# ctecka_stolni.net
KiCad netlist of a schematic drawn in EAGLE
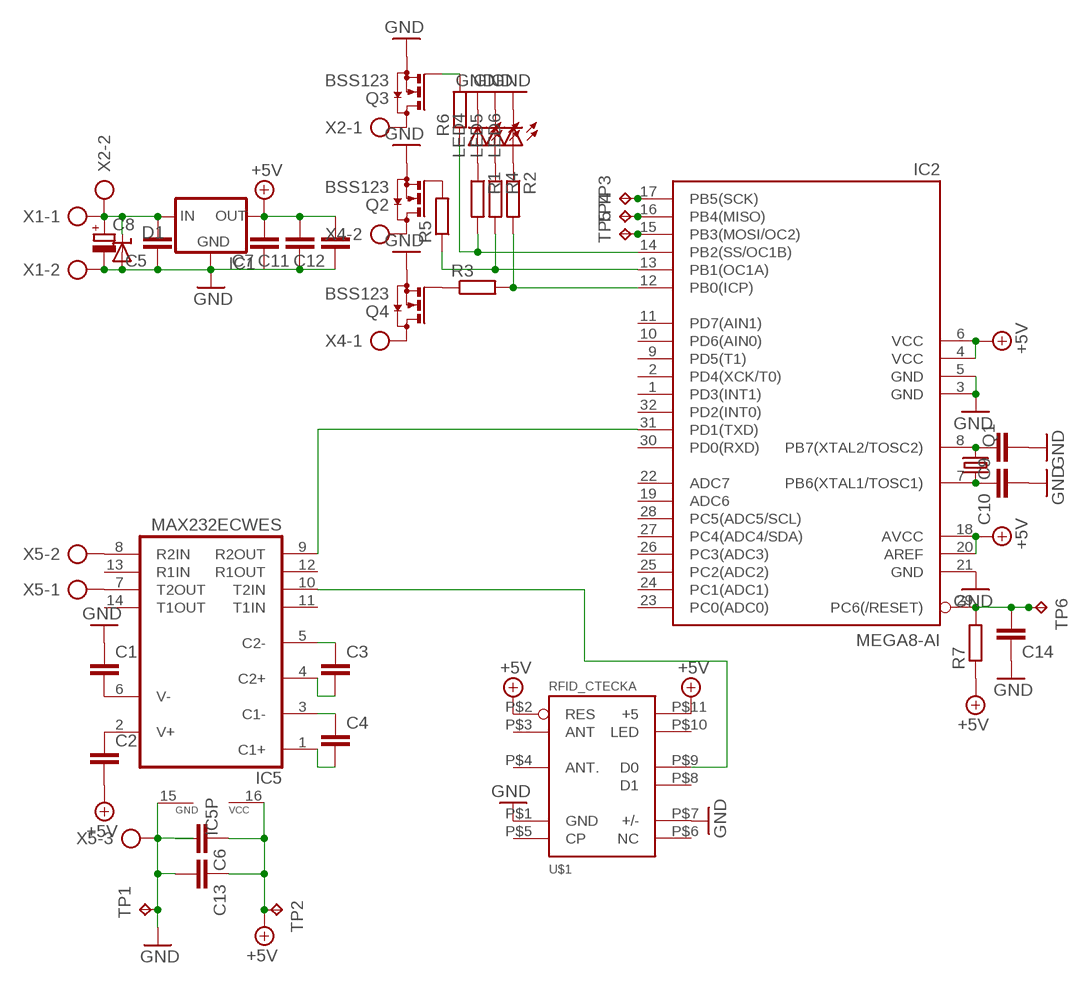
[diagram p0: schematic, sheet 1]

(export (version "E")
  (design (tool "Eeschema 10.0.6"))
  (components
    (comp (ref "C1")
      (value "C-EUC0603")
      (footprint "eagle-import:C0603")
      (libsource (lib "eagle-import") (part "C-EUC0603"))
    )
    (comp (ref "C2")
      (value "C-EUC0603")
      (footprint "eagle-import:C0603")
      (libsource (lib "eagle-import") (part "C-EUC0603"))
    )
    (comp (ref "C3")
      (value "C-EUC0603")
      (footprint "eagle-import:C0603")
      (libsource (lib "eagle-import") (part "C-EUC0603"))
    )
    (comp (ref "C4")
      (value "C-EUC0603")
      (footprint "eagle-import:C0603")
      (libsource (lib "eagle-import") (part "C-EUC0603"))
    )
    (comp (ref "C5")
      (value "C-EUC0603")
      (footprint "eagle-import:C0603")
      (libsource (lib "eagle-import") (part "C-EUC0603"))
    )
    (comp (ref "C6")
      (value "C-EUC0603")
      (footprint "eagle-import:C0603")
      (libsource (lib "eagle-import") (part "C-EUC0603"))
    )
    (comp (ref "C7")
      (value "C-EUC0603")
      (footprint "eagle-import:C0603")
      (libsource (lib "eagle-import") (part "C-EUC0603"))
    )
    (comp (ref "C8")
      (value "CPOL-EUSMCD")
      (footprint "eagle-import:SMC_D")
      (libsource (lib "eagle-import") (part "CPOL-EUSMCD"))
    )
    (comp (ref "C9")
      (value "C-EUC0603")
      (footprint "eagle-import:C0603")
      (libsource (lib "eagle-import") (part "C-EUC0603"))
    )
    (comp (ref "C10")
      (value "C-EUC0603")
      (footprint "eagle-import:C0603")
      (libsource (lib "eagle-import") (part "C-EUC0603"))
    )
    (comp (ref "C11")
      (value "C-EUC0603")
      (footprint "eagle-import:C0603")
      (libsource (lib "eagle-import") (part "C-EUC0603"))
    )
    (comp (ref "C12")
      (value "C-EUC0603")
      (footprint "eagle-import:C0603")
      (libsource (lib "eagle-import") (part "C-EUC0603"))
    )
    (comp (ref "C13")
      (value "C-EUC0603")
      (footprint "eagle-import:C0603")
      (libsource (lib "eagle-import") (part "C-EUC0603"))
    )
    (comp (ref "C14")
      (value "C-EUC0603")
      (footprint "eagle-import:C0603")
      (libsource (lib "eagle-import") (part "C-EUC0603"))
    )
    (comp (ref "D1")
      (value "SUPPRESSOR-SMBG")
      (footprint "eagle-import:SMBG")
      (libsource (lib "eagle-import") (part "SUPPRESSOR-SMBG"))
    )
    (comp (ref "IC1")
      (value "78LXXF")
      (footprint "eagle-import:SOT89R")
      (libsource (lib "eagle-import") (part "78LXXF"))
    )
    (comp (ref "IC2")
      (value "MEGA8-AI")
      (footprint "eagle-import:TQFP32-08")
      (libsource (lib "eagle-import") (part "MEGA8-AI"))
    )
    (comp (ref "IC5")
      (value "MAX232ECWES")
      (footprint "eagle-import:SO16")
      (libsource (lib "eagle-import") (part "MAX232ECWES"))
    )
    (comp (ref "LED4")
      (value "LEDCHIP-LED0805")
      (footprint "eagle-import:CHIP-LED0805")
      (libsource (lib "eagle-import") (part "LEDCHIP-LED0805"))
    )
    (comp (ref "LED5")
      (value "LEDCHIP-LED0805")
      (footprint "eagle-import:CHIP-LED0805")
      (libsource (lib "eagle-import") (part "LEDCHIP-LED0805"))
    )
    (comp (ref "LED6")
      (value "LEDCHIP-LED0805")
      (footprint "eagle-import:CHIP-LED0805")
      (libsource (lib "eagle-import") (part "LEDCHIP-LED0805"))
    )
    (comp (ref "Q1")
      (value "CRYSTALCTS406")
      (footprint "eagle-import:CTS406")
      (libsource (lib "eagle-import") (part "CRYSTALCTS406"))
    )
    (comp (ref "Q2")
      (value "BSS123")
      (footprint "eagle-import:SOT23")
      (libsource (lib "eagle-import") (part "BSS123"))
    )
    (comp (ref "Q3")
      (value "BSS123")
      (footprint "eagle-import:SOT23")
      (libsource (lib "eagle-import") (part "BSS123"))
    )
    (comp (ref "Q4")
      (value "BSS123")
      (footprint "eagle-import:SOT23")
      (libsource (lib "eagle-import") (part "BSS123"))
    )
    (comp (ref "R1")
      (value "R-EU_R0603")
      (footprint "eagle-import:R0603")
      (libsource (lib "eagle-import") (part "R-EU_R0603"))
    )
    (comp (ref "R2")
      (value "R-EU_R0603")
      (footprint "eagle-import:R0603")
      (libsource (lib "eagle-import") (part "R-EU_R0603"))
    )
    (comp (ref "R3")
      (value "R-EU_R0603")
      (footprint "eagle-import:R0603")
      (libsource (lib "eagle-import") (part "R-EU_R0603"))
    )
    (comp (ref "R4")
      (value "R-EU_R0603")
      (footprint "eagle-import:R0603")
      (libsource (lib "eagle-import") (part "R-EU_R0603"))
    )
    (comp (ref "R5")
      (value "R-EU_R0603")
      (footprint "eagle-import:R0603")
      (libsource (lib "eagle-import") (part "R-EU_R0603"))
    )
    (comp (ref "R6")
      (value "R-EU_R0603")
      (footprint "eagle-import:R0603")
      (libsource (lib "eagle-import") (part "R-EU_R0603"))
    )
    (comp (ref "R7")
      (value "R-EU_R0603")
      (footprint "eagle-import:R0603")
      (libsource (lib "eagle-import") (part "R-EU_R0603"))
    )
    (comp (ref "TP1")
      (value "TPB1,27")
      (footprint "eagle-import:B1,27")
      (libsource (lib "eagle-import") (part "TPB1,27"))
    )
    (comp (ref "TP2")
      (value "TPB1,27")
      (footprint "eagle-import:B1,27")
      (libsource (lib "eagle-import") (part "TPB1,27"))
    )
    (comp (ref "TP3")
      (value "TPB1,27")
      (footprint "eagle-import:B1,27")
      (libsource (lib "eagle-import") (part "TPB1,27"))
    )
    (comp (ref "TP4")
      (value "TPB1,27")
      (footprint "eagle-import:B1,27")
      (libsource (lib "eagle-import") (part "TPB1,27"))
    )
    (comp (ref "TP5")
      (value "TPB1,27")
      (footprint "eagle-import:B1,27")
      (libsource (lib "eagle-import") (part "TPB1,27"))
    )
    (comp (ref "TP6")
      (value "TPB1,27")
      (footprint "eagle-import:B1,27")
      (libsource (lib "eagle-import") (part "TPB1,27"))
    )
    (comp (ref "U$1")
      (value "RFID_CTECKA")
      (footprint "eagle-import:H")
      (libsource (lib "eagle-import") (part "RFID_CTECKA"))
    )
    (comp (ref "X1")
      (value "AK500/2")
      (footprint "eagle-import:AK500_2")
      (libsource (lib "eagle-import") (part "AK500/2"))
    )
    (comp (ref "X2")
      (value "AK500/2")
      (footprint "eagle-import:AK500_2")
      (libsource (lib "eagle-import") (part "AK500/2"))
    )
    (comp (ref "X4")
      (value "AK500/2")
      (footprint "eagle-import:AK500_2")
      (libsource (lib "eagle-import") (part "AK500/2"))
    )
    (comp (ref "X5")
      (value "AK500/3")
      (footprint "eagle-import:AK500_3")
      (libsource (lib "eagle-import") (part "AK500/3"))
    )
  )
  (nets
    (net (code "1") (name "+5V") (class "Default")
      (node (ref "C11") (pin "2") (pinfunction "2_2") (pintype "passive"))
      (node (ref "C12") (pin "2") (pinfunction "2_2") (pintype "passive"))
      (node (ref "C13") (pin "1") (pinfunction "1_1") (pintype "passive"))
      (node (ref "C2") (pin "2") (pinfunction "2_2") (pintype "passive"))
      (node (ref "C6") (pin "1") (pinfunction "1_1") (pintype "passive"))
      (node (ref "C7") (pin "2") (pinfunction "2_2") (pintype "passive"))
      (node (ref "IC1") (pin "2") (pinfunction "OUT_2") (pintype "passive"))
      (node (ref "IC2") (pin "18") (pinfunction "AVCC_18") (pintype "power_in"))
      (node (ref "IC2") (pin "20") (pinfunction "AREF_20") (pintype "passive"))
      (node (ref "IC2") (pin "4") (pinfunction "VCC_4") (pintype "power_in"))
      (node (ref "IC2") (pin "6") (pinfunction "VCC_6") (pintype "power_in"))
      (node (ref "IC5") (pin "16") (pinfunction "VCC_16") (pintype "power_in"))
      (node (ref "R7") (pin "1") (pinfunction "1_1") (pintype "passive"))
      (node (ref "TP2") (pin "TP") (pinfunction "TP_TP") (pintype "input"))
      (node (ref "U$1") (pin "P$11") (pinfunction "+5_P$11") (pintype "bidirectional"))
      (node (ref "U$1") (pin "P$2") (pinfunction "RES_P$2") (pintype "bidirectional"))
    )
    (net (code "2") (name "GND") (class "Default")
      (node (ref "C1") (pin "1") (pinfunction "1_1") (pintype "passive"))
      (node (ref "C10") (pin "2") (pinfunction "2_2") (pintype "passive"))
      (node (ref "C11") (pin "1") (pinfunction "1_1") (pintype "passive"))
      (node (ref "C12") (pin "1") (pinfunction "1_1") (pintype "passive"))
      (node (ref "C13") (pin "2") (pinfunction "2_2") (pintype "passive"))
      (node (ref "C14") (pin "1") (pinfunction "1_1") (pintype "passive"))
      (node (ref "C5") (pin "1") (pinfunction "1_1") (pintype "passive"))
      (node (ref "C6") (pin "2") (pinfunction "2_2") (pintype "passive"))
      (node (ref "C7") (pin "1") (pinfunction "1_1") (pintype "passive"))
      (node (ref "C8") (pin "-") (pinfunction "-_-") (pintype "passive"))
      (node (ref "C9") (pin "2") (pinfunction "2_2") (pintype "passive"))
      (node (ref "D1") (pin "A") (pinfunction "A_A") (pintype "passive"))
      (node (ref "IC1") (pin "3") (pinfunction "GND_3") (pintype "input"))
      (node (ref "IC2") (pin "21") (pinfunction "GND_21") (pintype "power_in"))
      (node (ref "IC2") (pin "3") (pinfunction "GND_3") (pintype "power_in"))
      (node (ref "IC2") (pin "5") (pinfunction "GND_5") (pintype "power_in"))
      (node (ref "IC5") (pin "15") (pinfunction "GND_15") (pintype "power_in"))
      (node (ref "LED4") (pin "C") (pinfunction "C_C") (pintype "passive"))
      (node (ref "LED5") (pin "C") (pinfunction "C_C") (pintype "passive"))
      (node (ref "LED6") (pin "C") (pinfunction "C_C") (pintype "passive"))
      (node (ref "Q2") (pin "2") (pinfunction "S_2") (pintype "passive"))
      (node (ref "Q3") (pin "2") (pinfunction "S_2") (pintype "passive"))
      (node (ref "Q4") (pin "2") (pinfunction "S_2") (pintype "passive"))
      (node (ref "TP1") (pin "TP") (pinfunction "TP_TP") (pintype "input"))
      (node (ref "U$1") (pin "P$1") (pinfunction "GND_P$1") (pintype "bidirectional"))
      (node (ref "U$1") (pin "P$7") (pinfunction "+/-_P$7") (pintype "bidirectional"))
      (node (ref "X1") (pin "2") (pinfunction "KL_2") (pintype "passive"))
      (node (ref "X5") (pin "3") (pinfunction "KL_3") (pintype "passive"))
    )
    (net (code "3") (name "Net-(IC1-IN)") (class "Default")
      (node (ref "C5") (pin "2") (pinfunction "2_2") (pintype "passive"))
      (node (ref "C8") (pin "+") (pinfunction "+_+") (pintype "passive"))
      (node (ref "D1") (pin "C") (pinfunction "C_C") (pintype "passive"))
      (node (ref "IC1") (pin "1") (pinfunction "IN_1") (pintype "input"))
      (node (ref "X1") (pin "1") (pinfunction "KL_1") (pintype "passive"))
      (node (ref "X2") (pin "2") (pinfunction "KL_2") (pintype "passive"))
    )
    (net (code "4") (name "Net-(IC2-PB0(ICP))") (class "Default")
      (node (ref "IC2") (pin "12") (pinfunction "PB0(ICP)_12") (pintype "bidirectional"))
      (node (ref "R2") (pin "2") (pinfunction "2_2") (pintype "passive"))
      (node (ref "R3") (pin "2") (pinfunction "2_2") (pintype "passive"))
    )
    (net (code "5") (name "Net-(IC2-PB1(OC1A))") (class "Default")
      (node (ref "IC2") (pin "13") (pinfunction "PB1(OC1A)_13") (pintype "bidirectional"))
      (node (ref "R4") (pin "2") (pinfunction "2_2") (pintype "passive"))
      (node (ref "R5") (pin "1") (pinfunction "1_1") (pintype "passive"))
    )
    (net (code "6") (name "Net-(IC2-PB2(SS{slash}OC1B))") (class "Default")
      (node (ref "IC2") (pin "14") (pinfunction "PB2(SS/OC1B)_14") (pintype "bidirectional"))
      (node (ref "R1") (pin "2") (pinfunction "2_2") (pintype "passive"))
      (node (ref "R6") (pin "1") (pinfunction "1_1") (pintype "passive"))
    )
    (net (code "7") (name "Net-(IC2-PB3(MOSI{slash}OC2))") (class "Default")
      (node (ref "IC2") (pin "15") (pinfunction "PB3(MOSI/OC2)_15") (pintype "bidirectional"))
      (node (ref "TP5") (pin "TP") (pinfunction "TP_TP") (pintype "input"))
    )
    (net (code "8") (name "Net-(IC2-PB4(MISO))") (class "Default")
      (node (ref "IC2") (pin "16") (pinfunction "PB4(MISO)_16") (pintype "bidirectional"))
      (node (ref "TP4") (pin "TP") (pinfunction "TP_TP") (pintype "input"))
    )
    (net (code "9") (name "Net-(IC2-PB5(SCK))") (class "Default")
      (node (ref "IC2") (pin "17") (pinfunction "PB5(SCK)_17") (pintype "bidirectional"))
      (node (ref "TP3") (pin "TP") (pinfunction "TP_TP") (pintype "input"))
    )
    (net (code "10") (name "Net-(IC2-PB6(XTAL1{slash}TOSC1))") (class "Default")
      (node (ref "C10") (pin "1") (pinfunction "1_1") (pintype "passive"))
      (node (ref "IC2") (pin "7") (pinfunction "PB6(XTAL1/TOSC1)_7") (pintype "bidirectional"))
      (node (ref "Q1") (pin "1") (pinfunction "1_1") (pintype "passive"))
    )
    (net (code "11") (name "Net-(IC2-PB7(XTAL2{slash}TOSC2))") (class "Default")
      (node (ref "C9") (pin "1") (pinfunction "1_1") (pintype "passive"))
      (node (ref "IC2") (pin "8") (pinfunction "PB7(XTAL2/TOSC2)_8") (pintype "bidirectional"))
      (node (ref "Q1") (pin "3") (pinfunction "2_3") (pintype "passive"))
    )
    (net (code "12") (name "Net-(IC2-PC6({slash}RESET))") (class "Default")
      (node (ref "C14") (pin "2") (pinfunction "2_2") (pintype "passive"))
      (node (ref "IC2") (pin "29") (pinfunction "PC6(/RESET)_29") (pintype "bidirectional"))
      (node (ref "R7") (pin "2") (pinfunction "2_2") (pintype "passive"))
      (node (ref "TP6") (pin "TP") (pinfunction "TP_TP") (pintype "input"))
    )
    (net (code "13") (name "Net-(IC2-PD1(TXD))") (class "Default")
      (node (ref "IC2") (pin "31") (pinfunction "PD1(TXD)_31") (pintype "bidirectional"))
      (node (ref "IC5") (pin "9") (pinfunction "R2OUT_9") (pintype "output"))
    )
    (net (code "14") (name "Net-(IC5A-C1+)") (class "Default")
      (node (ref "C4") (pin "2") (pinfunction "2_2") (pintype "passive"))
      (node (ref "IC5") (pin "1") (pinfunction "C1+_1") (pintype "bidirectional"))
    )
    (net (code "15") (name "Net-(IC5A-C1-)") (class "Default")
      (node (ref "C4") (pin "1") (pinfunction "1_1") (pintype "passive"))
      (node (ref "IC5") (pin "3") (pinfunction "C1-_3") (pintype "bidirectional"))
    )
    (net (code "16") (name "Net-(IC5A-C2+)") (class "Default")
      (node (ref "C3") (pin "2") (pinfunction "2_2") (pintype "passive"))
      (node (ref "IC5") (pin "4") (pinfunction "C2+_4") (pintype "bidirectional"))
    )
    (net (code "17") (name "Net-(IC5A-C2-)") (class "Default")
      (node (ref "C3") (pin "1") (pinfunction "1_1") (pintype "passive"))
      (node (ref "IC5") (pin "5") (pinfunction "C2-_5") (pintype "bidirectional"))
    )
    (net (code "18") (name "Net-(IC5A-R2IN)") (class "Default")
      (node (ref "IC5") (pin "8") (pinfunction "R2IN_8") (pintype "input"))
      (node (ref "X5") (pin "2") (pinfunction "KL_2") (pintype "passive"))
    )
    (net (code "19") (name "Net-(IC5A-T2IN)") (class "Default")
      (node (ref "IC5") (pin "10") (pinfunction "T2IN_10") (pintype "input"))
      (node (ref "U$1") (pin "P$9") (pinfunction "D0_P$9") (pintype "bidirectional"))
    )
    (net (code "20") (name "Net-(IC5A-T2OUT)") (class "Default")
      (node (ref "IC5") (pin "7") (pinfunction "T2OUT_7") (pintype "output"))
      (node (ref "X5") (pin "1") (pinfunction "KL_1") (pintype "passive"))
    )
    (net (code "21") (name "Net-(IC5A-V+)") (class "Default")
      (node (ref "C2") (pin "1") (pinfunction "1_1") (pintype "passive"))
      (node (ref "IC5") (pin "2") (pinfunction "V+_2") (pintype "bidirectional"))
    )
    (net (code "22") (name "Net-(IC5A-V-)") (class "Default")
      (node (ref "C1") (pin "2") (pinfunction "2_2") (pintype "passive"))
      (node (ref "IC5") (pin "6") (pinfunction "V-_6") (pintype "bidirectional"))
    )
    (net (code "23") (name "Net-(LED4-PadA)") (class "Default")
      (node (ref "LED4") (pin "A") (pinfunction "A_A") (pintype "passive"))
      (node (ref "R1") (pin "1") (pinfunction "1_1") (pintype "passive"))
    )
    (net (code "24") (name "Net-(LED5-PadA)") (class "Default")
      (node (ref "LED5") (pin "A") (pinfunction "A_A") (pintype "passive"))
      (node (ref "R4") (pin "1") (pinfunction "1_1") (pintype "passive"))
    )
    (net (code "25") (name "Net-(LED6-PadA)") (class "Default")
      (node (ref "LED6") (pin "A") (pinfunction "A_A") (pintype "passive"))
      (node (ref "R2") (pin "1") (pinfunction "1_1") (pintype "passive"))
    )
    (net (code "26") (name "Net-(Q2-D)") (class "Default")
      (node (ref "Q2") (pin "3") (pinfunction "D_3") (pintype "passive"))
      (node (ref "X4") (pin "2") (pinfunction "KL_2") (pintype "passive"))
    )
    (net (code "27") (name "Net-(Q2-G)") (class "Default")
      (node (ref "Q2") (pin "1") (pinfunction "G_1") (pintype "passive"))
      (node (ref "R5") (pin "2") (pinfunction "2_2") (pintype "passive"))
    )
    (net (code "28") (name "Net-(Q3-D)") (class "Default")
      (node (ref "Q3") (pin "3") (pinfunction "D_3") (pintype "passive"))
      (node (ref "X2") (pin "1") (pinfunction "KL_1") (pintype "passive"))
    )
    (net (code "29") (name "Net-(Q3-G)") (class "Default")
      (node (ref "Q3") (pin "1") (pinfunction "G_1") (pintype "passive"))
      (node (ref "R6") (pin "2") (pinfunction "2_2") (pintype "passive"))
    )
    (net (code "30") (name "Net-(Q4-D)") (class "Default")
      (node (ref "Q4") (pin "3") (pinfunction "D_3") (pintype "passive"))
      (node (ref "X4") (pin "1") (pinfunction "KL_1") (pintype "passive"))
    )
    (net (code "31") (name "Net-(Q4-G)") (class "Default")
      (node (ref "Q4") (pin "1") (pinfunction "G_1") (pintype "passive"))
      (node (ref "R3") (pin "1") (pinfunction "1_1") (pintype "passive"))
    )
    (net (code "32") (name "unconnected-(IC2-ADC6-Pad19)") (class "Default")
      (node (ref "IC2") (pin "19") (pinfunction "ADC6_19") (pintype "bidirectional"))
    )
    (net (code "33") (name "unconnected-(IC2-ADC7-Pad22)") (class "Default")
      (node (ref "IC2") (pin "22") (pinfunction "ADC7_22") (pintype "bidirectional"))
    )
    (net (code "34") (name "unconnected-(IC2-PC0(ADC0)-Pad23)") (class "Default")
      (node (ref "IC2") (pin "23") (pinfunction "PC0(ADC0)_23") (pintype "bidirectional"))
    )
    (net (code "35") (name "unconnected-(IC2-PC1(ADC1)-Pad24)") (class "Default")
      (node (ref "IC2") (pin "24") (pinfunction "PC1(ADC1)_24") (pintype "bidirectional"))
    )
    (net (code "36") (name "unconnected-(IC2-PC2(ADC2)-Pad25)") (class "Default")
      (node (ref "IC2") (pin "25") (pinfunction "PC2(ADC2)_25") (pintype "bidirectional"))
    )
    (net (code "37") (name "unconnected-(IC2-PC3(ADC3)-Pad26)") (class "Default")
      (node (ref "IC2") (pin "26") (pinfunction "PC3(ADC3)_26") (pintype "bidirectional"))
    )
    (net (code "38") (name "unconnected-(IC2-PC4(ADC4{slash}SDA)-Pad27)") (class "Default")
      (node (ref "IC2") (pin "27") (pinfunction "PC4(ADC4/SDA)_27") (pintype "bidirectional"))
    )
    (net (code "39") (name "unconnected-(IC2-PC5(ADC5{slash}SCL)-Pad28)") (class "Default")
      (node (ref "IC2") (pin "28") (pinfunction "PC5(ADC5/SCL)_28") (pintype "bidirectional"))
    )
    (net (code "40") (name "unconnected-(IC2-PD0(RXD)-Pad30)") (class "Default")
      (node (ref "IC2") (pin "30") (pinfunction "PD0(RXD)_30") (pintype "bidirectional"))
    )
    (net (code "41") (name "unconnected-(IC2-PD2(INT0)-Pad32)") (class "Default")
      (node (ref "IC2") (pin "32") (pinfunction "PD2(INT0)_32") (pintype "bidirectional"))
    )
    (net (code "42") (name "unconnected-(IC2-PD3(INT1)-Pad1)") (class "Default")
      (node (ref "IC2") (pin "1") (pinfunction "PD3(INT1)_1") (pintype "bidirectional"))
    )
    (net (code "43") (name "unconnected-(IC2-PD4(XCK{slash}T0)-Pad2)") (class "Default")
      (node (ref "IC2") (pin "2") (pinfunction "PD4(XCK/T0)_2") (pintype "bidirectional"))
    )
    (net (code "44") (name "unconnected-(IC2-PD5(T1)-Pad9)") (class "Default")
      (node (ref "IC2") (pin "9") (pinfunction "PD5(T1)_9") (pintype "bidirectional"))
    )
    (net (code "45") (name "unconnected-(IC2-PD6(AIN0)-Pad10)") (class "Default")
      (node (ref "IC2") (pin "10") (pinfunction "PD6(AIN0)_10") (pintype "bidirectional"))
    )
    (net (code "46") (name "unconnected-(IC2-PD7(AIN1)-Pad11)") (class "Default")
      (node (ref "IC2") (pin "11") (pinfunction "PD7(AIN1)_11") (pintype "bidirectional"))
    )
    (net (code "47") (name "unconnected-(IC5A-R1IN-Pad13)") (class "Default")
      (node (ref "IC5") (pin "13") (pinfunction "R1IN_13") (pintype "input"))
    )
    (net (code "48") (name "unconnected-(IC5A-R1OUT-Pad12)") (class "Default")
      (node (ref "IC5") (pin "12") (pinfunction "R1OUT_12") (pintype "output"))
    )
    (net (code "49") (name "unconnected-(IC5A-T1IN-Pad11)") (class "Default")
      (node (ref "IC5") (pin "11") (pinfunction "T1IN_11") (pintype "input"))
    )
    (net (code "50") (name "unconnected-(IC5A-T1OUT-Pad14)") (class "Default")
      (node (ref "IC5") (pin "14") (pinfunction "T1OUT_14") (pintype "output"))
    )
    (net (code "51") (name "unconnected-(U$1-ANT-PadP$3)") (class "Default")
      (node (ref "U$1") (pin "P$3") (pinfunction "ANT_P$3") (pintype "bidirectional"))
    )
    (net (code "52") (name "unconnected-(U$1-ANT.-PadP$4)") (class "Default")
      (node (ref "U$1") (pin "P$4") (pinfunction "ANT._P$4") (pintype "bidirectional"))
    )
    (net (code "53") (name "unconnected-(U$1-CP-PadP$5)") (class "Default")
      (node (ref "U$1") (pin "P$5") (pinfunction "CP_P$5") (pintype "bidirectional"))
    )
    (net (code "54") (name "unconnected-(U$1-D1-PadP$8)") (class "Default")
      (node (ref "U$1") (pin "P$8") (pinfunction "D1_P$8") (pintype "bidirectional"))
    )
    (net (code "55") (name "unconnected-(U$1-LED-PadP$10)") (class "Default")
      (node (ref "U$1") (pin "P$10") (pinfunction "LED_P$10") (pintype "bidirectional"))
    )
    (net (code "56") (name "unconnected-(U$1-NC-PadP$6)") (class "Default")
      (node (ref "U$1") (pin "P$6") (pinfunction "NC_P$6") (pintype "bidirectional"))
    )
  )
)
